# expbox.net
KiCad netlist of a schematic drawn in EAGLE
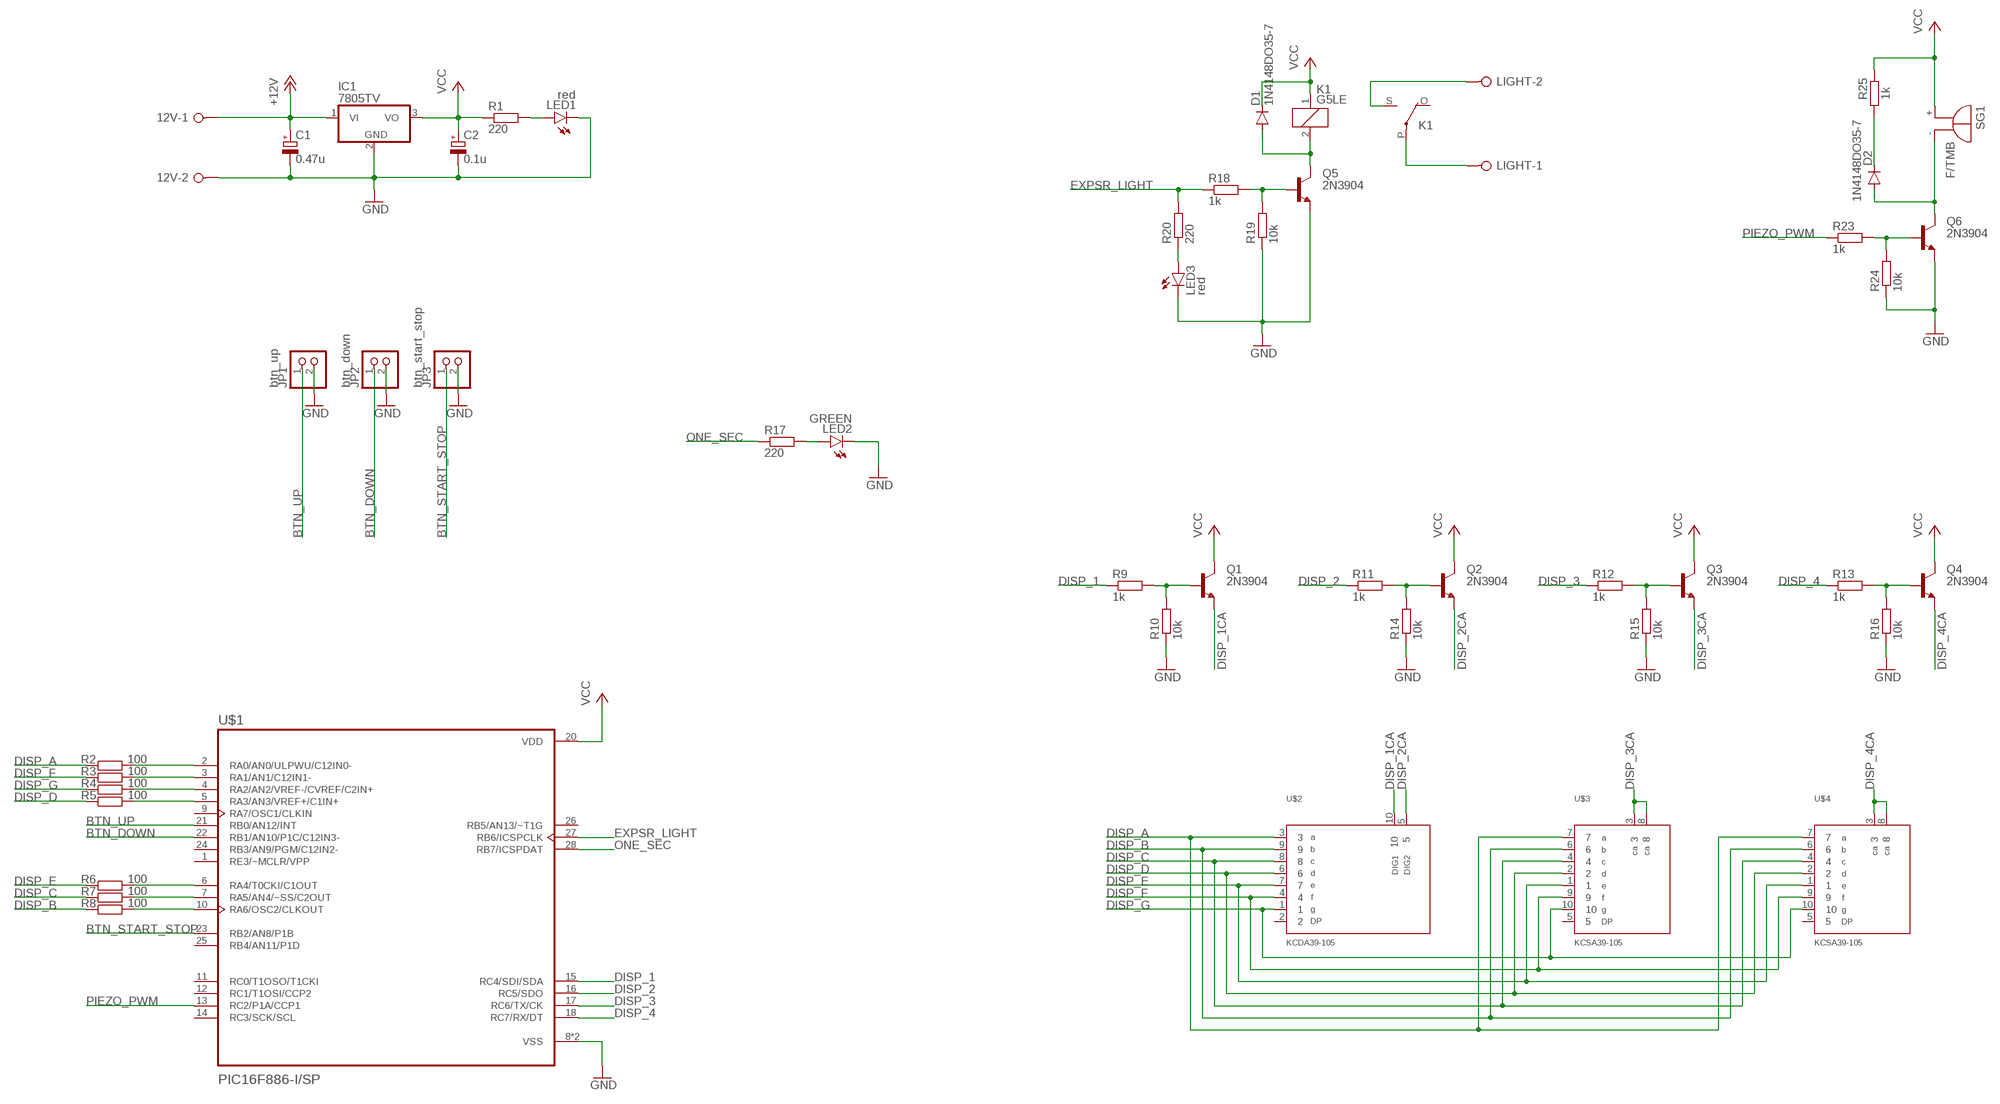
[diagram p0: schematic, sheet 1]

(export (version "E")
  (design (tool "Eeschema 10.0.6"))
  (components
    (comp (ref "12V")
      (value "W237-02P")
      (footprint "eagle-import:W237-132")
      (libsource (lib "eagle-import") (part "W237-02P"))
    )
    (comp (ref "C1")
      (value "0.47u")
      (footprint "eagle-import:E2,5-5")
      (libsource (lib "eagle-import") (part "CPOL-EUE2.5-5"))
    )
    (comp (ref "C2")
      (value "0.1u")
      (footprint "eagle-import:E2-4")
      (libsource (lib "eagle-import") (part "CPOL-EUE2-4"))
    )
    (comp (ref "D1")
      (value "1N4148DO35-7")
      (footprint "eagle-import:DO35-7")
      (libsource (lib "eagle-import") (part "1N4148DO35-7"))
    )
    (comp (ref "D2")
      (value "1N4148DO35-7")
      (footprint "eagle-import:DO35-7")
      (libsource (lib "eagle-import") (part "1N4148DO35-7"))
    )
    (comp (ref "IC1")
      (value "7805TV")
      (footprint "eagle-import:TO220V")
      (libsource (lib "eagle-import") (part "78TV05"))
    )
    (comp (ref "JP1")
      (value "btn_up")
      (footprint "eagle-import:1X02")
      (libsource (lib "eagle-import") (part "PINHD-1X2"))
    )
    (comp (ref "JP2")
      (value "btn_down")
      (footprint "eagle-import:1X02")
      (libsource (lib "eagle-import") (part "PINHD-1X2"))
    )
    (comp (ref "JP3")
      (value "btn_start_stop")
      (footprint "eagle-import:1X02")
      (libsource (lib "eagle-import") (part "PINHD-1X2"))
    )
    (comp (ref "K1")
      (value "G5LE")
      (footprint "eagle-import:G5LE")
      (libsource (lib "eagle-import") (part "G5LE"))
    )
    (comp (ref "LED1")
      (value "red")
      (footprint "eagle-import:LED3MM")
      (libsource (lib "eagle-import") (part "LED3MM"))
    )
    (comp (ref "LED2")
      (value "GREEN")
      (footprint "eagle-import:1206")
      (libsource (lib "eagle-import") (part "LEDSMT1206"))
    )
    (comp (ref "LED3")
      (value "red")
      (footprint "eagle-import:LED3MM")
      (libsource (lib "eagle-import") (part "LED3MM"))
    )
    (comp (ref "LIGHT")
      (value "W237-02P")
      (footprint "eagle-import:W237-132")
      (libsource (lib "eagle-import") (part "W237-02P"))
    )
    (comp (ref "Q1")
      (value "2N3904")
      (footprint "eagle-import:SOT23-BEC")
      (libsource (lib "eagle-import") (part "BC850SMD"))
    )
    (comp (ref "Q2")
      (value "2N3904")
      (footprint "eagle-import:SOT23-BEC")
      (libsource (lib "eagle-import") (part "BC850SMD"))
    )
    (comp (ref "Q3")
      (value "2N3904")
      (footprint "eagle-import:SOT23-BEC")
      (libsource (lib "eagle-import") (part "BC850SMD"))
    )
    (comp (ref "Q4")
      (value "2N3904")
      (footprint "eagle-import:SOT23-BEC")
      (libsource (lib "eagle-import") (part "BC850SMD"))
    )
    (comp (ref "Q5")
      (value "2N3904")
      (footprint "eagle-import:SOT23-BEC")
      (libsource (lib "eagle-import") (part "BC850SMD"))
    )
    (comp (ref "Q6")
      (value "2N3904")
      (footprint "eagle-import:SOT23-BEC")
      (libsource (lib "eagle-import") (part "BC850SMD"))
    )
    (comp (ref "R1")
      (value "220")
      (footprint "eagle-import:R0805")
      (libsource (lib "eagle-import") (part "R-EU_R0805"))
    )
    (comp (ref "R2")
      (value "100")
      (footprint "eagle-import:M1206")
      (libsource (lib "eagle-import") (part "R-EU_M1206"))
    )
    (comp (ref "R3")
      (value "100")
      (footprint "eagle-import:M1206")
      (libsource (lib "eagle-import") (part "R-EU_M1206"))
    )
    (comp (ref "R4")
      (value "100")
      (footprint "eagle-import:M1206")
      (libsource (lib "eagle-import") (part "R-EU_M1206"))
    )
    (comp (ref "R5")
      (value "100")
      (footprint "eagle-import:M1206")
      (libsource (lib "eagle-import") (part "R-EU_M1206"))
    )
    (comp (ref "R6")
      (value "100")
      (footprint "eagle-import:M1206")
      (libsource (lib "eagle-import") (part "R-EU_M1206"))
    )
    (comp (ref "R7")
      (value "100")
      (footprint "eagle-import:M1206")
      (libsource (lib "eagle-import") (part "R-EU_M1206"))
    )
    (comp (ref "R8")
      (value "100")
      (footprint "eagle-import:M1206")
      (libsource (lib "eagle-import") (part "R-EU_M1206"))
    )
    (comp (ref "R9")
      (value "1k")
      (footprint "eagle-import:R0805")
      (libsource (lib "eagle-import") (part "R-EU_R0805"))
    )
    (comp (ref "R10")
      (value "10k")
      (footprint "eagle-import:R0805")
      (libsource (lib "eagle-import") (part "R-EU_R0805"))
    )
    (comp (ref "R11")
      (value "1k")
      (footprint "eagle-import:R0805")
      (libsource (lib "eagle-import") (part "R-EU_R0805"))
    )
    (comp (ref "R12")
      (value "1k")
      (footprint "eagle-import:R0805")
      (libsource (lib "eagle-import") (part "R-EU_R0805"))
    )
    (comp (ref "R13")
      (value "1k")
      (footprint "eagle-import:R0805")
      (libsource (lib "eagle-import") (part "R-EU_R0805"))
    )
    (comp (ref "R14")
      (value "10k")
      (footprint "eagle-import:R0805")
      (libsource (lib "eagle-import") (part "R-EU_R0805"))
    )
    (comp (ref "R15")
      (value "10k")
      (footprint "eagle-import:R0805")
      (libsource (lib "eagle-import") (part "R-EU_R0805"))
    )
    (comp (ref "R16")
      (value "10k")
      (footprint "eagle-import:R0805")
      (libsource (lib "eagle-import") (part "R-EU_R0805"))
    )
    (comp (ref "R17")
      (value "220")
      (footprint "eagle-import:R0805")
      (libsource (lib "eagle-import") (part "R-EU_R0805"))
    )
    (comp (ref "R18")
      (value "1k")
      (footprint "eagle-import:R0805")
      (libsource (lib "eagle-import") (part "R-EU_R0805"))
    )
    (comp (ref "R19")
      (value "10k")
      (footprint "eagle-import:R0805")
      (libsource (lib "eagle-import") (part "R-EU_R0805"))
    )
    (comp (ref "R20")
      (value "220")
      (footprint "eagle-import:R0805")
      (libsource (lib "eagle-import") (part "R-EU_R0805"))
    )
    (comp (ref "R23")
      (value "1k")
      (footprint "eagle-import:R0805")
      (libsource (lib "eagle-import") (part "R-EU_R0805"))
    )
    (comp (ref "R24")
      (value "10k")
      (footprint "eagle-import:R0805")
      (libsource (lib "eagle-import") (part "R-EU_R0805"))
    )
    (comp (ref "R25")
      (value "1k")
      (footprint "eagle-import:R0805")
      (libsource (lib "eagle-import") (part "R-EU_R0805"))
    )
    (comp (ref "SG1")
      (value "F/TMB")
      (footprint "eagle-import:F_TMB")
      (libsource (lib "eagle-import") (part "F/TMB"))
    )
    (comp (ref "U$1")
      (value "PIC16F886-I/SP")
      (footprint "eagle-import:DIP762W46P254L3467H457Q28")
      (fields (field (name "MF") "Microchip"))
      (libsource (lib "eagle-import") (part "PIC16F886-I/SP"))
    )
    (comp (ref "U$2")
      (value "KCDA39-105")
      (footprint "eagle-import:KCDA39-105")
      (libsource (lib "eagle-import") (part "KCDA39-105"))
    )
    (comp (ref "U$3")
      (value "KCSA39-105")
      (footprint "eagle-import:KCSA39-105")
      (libsource (lib "eagle-import") (part "KCSA39-105"))
    )
    (comp (ref "U$4")
      (value "KCSA39-105")
      (footprint "eagle-import:KCSA39-105")
      (libsource (lib "eagle-import") (part "KCSA39-105"))
    )
  )
  (nets
    (net (code "1") (name "+12V") (class "Default")
      (node (ref "12V") (pin "1") (pinfunction "KL_1") (pintype "passive"))
      (node (ref "C1") (pin "+") (pinfunction "+_+") (pintype "passive"))
      (node (ref "IC1") (pin "1") (pinfunction "VI_1") (pintype "input"))
    )
    (net (code "2") (name "/BTN_DOWN") (class "Default")
      (node (ref "JP2") (pin "1") (pinfunction "1_1") (pintype "passive"))
      (node (ref "U$1") (pin "22") (pinfunction "RB1/AN10/P1C/C12IN3-_22") (pintype "input"))
    )
    (net (code "3") (name "/BTN_START_STOP") (class "Default")
      (node (ref "JP3") (pin "1") (pinfunction "1_1") (pintype "passive"))
      (node (ref "U$1") (pin "23") (pinfunction "RB2/AN8/P1B_23") (pintype "bidirectional"))
    )
    (net (code "4") (name "/BTN_UP") (class "Default")
      (node (ref "JP1") (pin "1") (pinfunction "1_1") (pintype "passive"))
      (node (ref "U$1") (pin "21") (pinfunction "RB0/AN12/INT_21") (pintype "input"))
    )
    (net (code "5") (name "/DISP_1") (class "Default")
      (node (ref "R9") (pin "1") (pinfunction "1_1") (pintype "passive"))
      (node (ref "U$1") (pin "15") (pinfunction "RC4/SDI/SDA_15") (pintype "bidirectional"))
    )
    (net (code "6") (name "/DISP_1CA") (class "Default")
      (node (ref "Q1") (pin "E") (pinfunction "E_E") (pintype "passive"))
      (node (ref "U$2") (pin "10") (pinfunction "10_10") (pintype "bidirectional"))
    )
    (net (code "7") (name "/DISP_2") (class "Default")
      (node (ref "R11") (pin "1") (pinfunction "1_1") (pintype "passive"))
      (node (ref "U$1") (pin "16") (pinfunction "RC5/SDO_16") (pintype "bidirectional"))
    )
    (net (code "8") (name "/DISP_2CA") (class "Default")
      (node (ref "Q2") (pin "E") (pinfunction "E_E") (pintype "passive"))
      (node (ref "U$2") (pin "5") (pinfunction "5_5") (pintype "bidirectional"))
    )
    (net (code "9") (name "/DISP_3") (class "Default")
      (node (ref "R12") (pin "1") (pinfunction "1_1") (pintype "passive"))
      (node (ref "U$1") (pin "17") (pinfunction "RC6/TX/CK_17") (pintype "bidirectional"))
    )
    (net (code "10") (name "/DISP_3CA") (class "Default")
      (node (ref "Q3") (pin "E") (pinfunction "E_E") (pintype "passive"))
      (node (ref "U$3") (pin "3") (pinfunction "3_3") (pintype "bidirectional"))
      (node (ref "U$3") (pin "8") (pinfunction "8_8") (pintype "bidirectional"))
    )
    (net (code "11") (name "/DISP_4") (class "Default")
      (node (ref "R13") (pin "1") (pinfunction "1_1") (pintype "passive"))
      (node (ref "U$1") (pin "18") (pinfunction "RC7/RX/DT_18") (pintype "bidirectional"))
    )
    (net (code "12") (name "/DISP_4CA") (class "Default")
      (node (ref "Q4") (pin "E") (pinfunction "E_E") (pintype "passive"))
      (node (ref "U$4") (pin "3") (pinfunction "3_3") (pintype "bidirectional"))
      (node (ref "U$4") (pin "8") (pinfunction "8_8") (pintype "bidirectional"))
    )
    (net (code "13") (name "/DISP_A") (class "Default")
      (node (ref "R2") (pin "1") (pinfunction "1_1") (pintype "passive"))
      (node (ref "U$2") (pin "3") (pinfunction "3_3") (pintype "bidirectional"))
      (node (ref "U$3") (pin "7") (pinfunction "7_7") (pintype "bidirectional"))
      (node (ref "U$4") (pin "7") (pinfunction "7_7") (pintype "bidirectional"))
    )
    (net (code "14") (name "/DISP_B") (class "Default")
      (node (ref "R8") (pin "1") (pinfunction "1_1") (pintype "passive"))
      (node (ref "U$2") (pin "9") (pinfunction "9_9") (pintype "bidirectional"))
      (node (ref "U$3") (pin "6") (pinfunction "6_6") (pintype "bidirectional"))
      (node (ref "U$4") (pin "6") (pinfunction "6_6") (pintype "bidirectional"))
    )
    (net (code "15") (name "/DISP_C") (class "Default")
      (node (ref "R7") (pin "1") (pinfunction "1_1") (pintype "passive"))
      (node (ref "U$2") (pin "8") (pinfunction "8_8") (pintype "bidirectional"))
      (node (ref "U$3") (pin "4") (pinfunction "4_4") (pintype "bidirectional"))
      (node (ref "U$4") (pin "4") (pinfunction "4_4") (pintype "bidirectional"))
    )
    (net (code "16") (name "/DISP_D") (class "Default")
      (node (ref "R5") (pin "1") (pinfunction "1_1") (pintype "passive"))
      (node (ref "U$2") (pin "6") (pinfunction "6_6") (pintype "bidirectional"))
      (node (ref "U$3") (pin "2") (pinfunction "2_2") (pintype "bidirectional"))
      (node (ref "U$4") (pin "2") (pinfunction "2_2") (pintype "bidirectional"))
    )
    (net (code "17") (name "/DISP_E") (class "Default")
      (node (ref "R6") (pin "1") (pinfunction "1_1") (pintype "passive"))
      (node (ref "U$2") (pin "7") (pinfunction "7_7") (pintype "bidirectional"))
      (node (ref "U$3") (pin "1") (pinfunction "1_1") (pintype "bidirectional"))
      (node (ref "U$4") (pin "1") (pinfunction "1_1") (pintype "bidirectional"))
    )
    (net (code "18") (name "/DISP_F") (class "Default")
      (node (ref "R3") (pin "1") (pinfunction "1_1") (pintype "passive"))
      (node (ref "U$2") (pin "4") (pinfunction "4_4") (pintype "bidirectional"))
      (node (ref "U$3") (pin "9") (pinfunction "9_9") (pintype "bidirectional"))
      (node (ref "U$4") (pin "9") (pinfunction "9_9") (pintype "bidirectional"))
    )
    (net (code "19") (name "/DISP_G") (class "Default")
      (node (ref "R4") (pin "1") (pinfunction "1_1") (pintype "passive"))
      (node (ref "U$2") (pin "1") (pinfunction "1_1") (pintype "bidirectional"))
      (node (ref "U$3") (pin "10") (pinfunction "10_10") (pintype "bidirectional"))
      (node (ref "U$4") (pin "10") (pinfunction "10_10") (pintype "bidirectional"))
    )
    (net (code "20") (name "/EXPSR_LIGHT") (class "Default")
      (node (ref "R18") (pin "1") (pinfunction "1_1") (pintype "passive"))
      (node (ref "R20") (pin "2") (pinfunction "2_2") (pintype "passive"))
      (node (ref "U$1") (pin "27") (pinfunction "RB6/ICSPCLK_27") (pintype "bidirectional"))
    )
    (net (code "21") (name "/ONE_SEC") (class "Default")
      (node (ref "R17") (pin "1") (pinfunction "1_1") (pintype "passive"))
      (node (ref "U$1") (pin "28") (pinfunction "RB7/ICSPDAT_28") (pintype "bidirectional"))
    )
    (net (code "22") (name "/PIEZO_PWM") (class "Default")
      (node (ref "R23") (pin "1") (pinfunction "1_1") (pintype "passive"))
      (node (ref "U$1") (pin "13") (pinfunction "RC2/P1A/CCP1_13") (pintype "bidirectional"))
    )
    (net (code "23") (name "GND") (class "Default")
      (node (ref "12V") (pin "2") (pinfunction "KL_2") (pintype "passive"))
      (node (ref "C1") (pin "-") (pinfunction "-_-") (pintype "passive"))
      (node (ref "C2") (pin "-") (pinfunction "-_-") (pintype "passive"))
      (node (ref "IC1") (pin "2") (pinfunction "GND_2") (pintype "passive"))
      (node (ref "JP1") (pin "2") (pinfunction "2_2") (pintype "passive"))
      (node (ref "JP2") (pin "2") (pinfunction "2_2") (pintype "passive"))
      (node (ref "JP3") (pin "2") (pinfunction "2_2") (pintype "passive"))
      (node (ref "LED1") (pin "K") (pinfunction "C_K") (pintype "passive"))
      (node (ref "LED2") (pin "C") (pinfunction "C_C") (pintype "passive"))
      (node (ref "LED3") (pin "K") (pinfunction "C_K") (pintype "passive"))
      (node (ref "Q5") (pin "E") (pinfunction "E_E") (pintype "passive"))
      (node (ref "Q6") (pin "E") (pinfunction "E_E") (pintype "passive"))
      (node (ref "R10") (pin "1") (pinfunction "1_1") (pintype "passive"))
      (node (ref "R14") (pin "1") (pinfunction "1_1") (pintype "passive"))
      (node (ref "R15") (pin "1") (pinfunction "1_1") (pintype "passive"))
      (node (ref "R16") (pin "1") (pinfunction "1_1") (pintype "passive"))
      (node (ref "R19") (pin "1") (pinfunction "1_1") (pintype "passive"))
      (node (ref "R24") (pin "1") (pinfunction "1_1") (pintype "passive"))
      (node (ref "U$1") (pin "19") (pinfunction "VSS_19") (pintype "power_in"))
      (node (ref "U$1") (pin "8") (pinfunction "VSS_8") (pintype "power_in"))
    )
    (net (code "24") (name "Net-(D1-PadA)") (class "Default")
      (node (ref "D1") (pin "A") (pinfunction "A_A") (pintype "passive"))
      (node (ref "K1") (pin "2") (pinfunction "2_2") (pintype "passive"))
      (node (ref "Q5") (pin "C") (pinfunction "C_C") (pintype "passive"))
    )
    (net (code "25") (name "Net-(D2-PadA)") (class "Default")
      (node (ref "D2") (pin "A") (pinfunction "A_A") (pintype "passive"))
      (node (ref "Q6") (pin "C") (pinfunction "C_C") (pintype "passive"))
      (node (ref "SG1") (pin "-") (pinfunction "-_-") (pintype "passive"))
    )
    (net (code "26") (name "Net-(D2-PadC)") (class "Default")
      (node (ref "D2") (pin "C") (pinfunction "C_C") (pintype "passive"))
      (node (ref "R25") (pin "1") (pinfunction "1_1") (pintype "passive"))
    )
    (net (code "27") (name "Net-(LED1-PadA)") (class "Default")
      (node (ref "LED1") (pin "A") (pinfunction "A_A") (pintype "passive"))
      (node (ref "R1") (pin "2") (pinfunction "2_2") (pintype "passive"))
    )
    (net (code "28") (name "Net-(LED2-PadA)") (class "Default")
      (node (ref "LED2") (pin "A") (pinfunction "A_A") (pintype "passive"))
      (node (ref "R17") (pin "2") (pinfunction "2_2") (pintype "passive"))
    )
    (net (code "29") (name "Net-(LED3-PadA)") (class "Default")
      (node (ref "LED3") (pin "A") (pinfunction "A_A") (pintype "passive"))
      (node (ref "R20") (pin "1") (pinfunction "1_1") (pintype "passive"))
    )
    (net (code "30") (name "Net-(LIGHTA-KL)") (class "Default")
      (node (ref "K1") (pin "P") (pinfunction "P_P") (pintype "passive"))
      (node (ref "LIGHT") (pin "1") (pinfunction "KL_1") (pintype "passive"))
    )
    (net (code "31") (name "Net-(LIGHTB-KL)") (class "Default")
      (node (ref "K1") (pin "S") (pinfunction "S_S") (pintype "passive"))
      (node (ref "LIGHT") (pin "2") (pinfunction "KL_2") (pintype "passive"))
    )
    (net (code "32") (name "Net-(Q1-PadB)") (class "Default")
      (node (ref "Q1") (pin "B") (pinfunction "B_B") (pintype "passive"))
      (node (ref "R10") (pin "2") (pinfunction "2_2") (pintype "passive"))
      (node (ref "R9") (pin "2") (pinfunction "2_2") (pintype "passive"))
    )
    (net (code "33") (name "Net-(Q2-PadB)") (class "Default")
      (node (ref "Q2") (pin "B") (pinfunction "B_B") (pintype "passive"))
      (node (ref "R11") (pin "2") (pinfunction "2_2") (pintype "passive"))
      (node (ref "R14") (pin "2") (pinfunction "2_2") (pintype "passive"))
    )
    (net (code "34") (name "Net-(Q3-PadB)") (class "Default")
      (node (ref "Q3") (pin "B") (pinfunction "B_B") (pintype "passive"))
      (node (ref "R12") (pin "2") (pinfunction "2_2") (pintype "passive"))
      (node (ref "R15") (pin "2") (pinfunction "2_2") (pintype "passive"))
    )
    (net (code "35") (name "Net-(Q4-PadB)") (class "Default")
      (node (ref "Q4") (pin "B") (pinfunction "B_B") (pintype "passive"))
      (node (ref "R13") (pin "2") (pinfunction "2_2") (pintype "passive"))
      (node (ref "R16") (pin "2") (pinfunction "2_2") (pintype "passive"))
    )
    (net (code "36") (name "Net-(Q5-PadB)") (class "Default")
      (node (ref "Q5") (pin "B") (pinfunction "B_B") (pintype "passive"))
      (node (ref "R18") (pin "2") (pinfunction "2_2") (pintype "passive"))
      (node (ref "R19") (pin "2") (pinfunction "2_2") (pintype "passive"))
    )
    (net (code "37") (name "Net-(Q6-PadB)") (class "Default")
      (node (ref "Q6") (pin "B") (pinfunction "B_B") (pintype "passive"))
      (node (ref "R23") (pin "2") (pinfunction "2_2") (pintype "passive"))
      (node (ref "R24") (pin "2") (pinfunction "2_2") (pintype "passive"))
    )
    (net (code "38") (name "Net-(U$1-RA0{slash}AN0{slash}ULPWU{slash}C12IN0-)") (class "Default")
      (node (ref "R2") (pin "2") (pinfunction "2_2") (pintype "passive"))
      (node (ref "U$1") (pin "2") (pinfunction "RA0/AN0/ULPWU/C12IN0-_2") (pintype "input"))
    )
    (net (code "39") (name "Net-(U$1-RA1{slash}AN1{slash}C12IN1-)") (class "Default")
      (node (ref "R3") (pin "2") (pinfunction "2_2") (pintype "passive"))
      (node (ref "U$1") (pin "3") (pinfunction "RA1/AN1/C12IN1-_3") (pintype "input"))
    )
    (net (code "40") (name "Net-(U$1-RA2{slash}AN2{slash}VREF-{slash}CVREF{slash}C2IN+)") (class "Default")
      (node (ref "R4") (pin "2") (pinfunction "2_2") (pintype "passive"))
      (node (ref "U$1") (pin "4") (pinfunction "RA2/AN2/VREF-/CVREF/C2IN+_4") (pintype "input"))
    )
    (net (code "41") (name "Net-(U$1-RA3{slash}AN3{slash}VREF+{slash}C1IN+)") (class "Default")
      (node (ref "R5") (pin "2") (pinfunction "2_2") (pintype "passive"))
      (node (ref "U$1") (pin "5") (pinfunction "RA3/AN3/VREF+/C1IN+_5") (pintype "input"))
    )
    (net (code "42") (name "Net-(U$1-RA4{slash}T0CKI{slash}C1OUT)") (class "Default")
      (node (ref "R6") (pin "2") (pinfunction "2_2") (pintype "passive"))
      (node (ref "U$1") (pin "6") (pinfunction "RA4/T0CKI/C1OUT_6") (pintype "bidirectional"))
    )
    (net (code "43") (name "Net-(U$1-RA5{slash}AN4{slash}~{SS{slash}C2OUT})") (class "Default")
      (node (ref "R7") (pin "2") (pinfunction "2_2") (pintype "passive"))
      (node (ref "U$1") (pin "7") (pinfunction "RA5/AN4/~{SS/C2OUT}_7") (pintype "bidirectional"))
    )
    (net (code "44") (name "Net-(U$1-RA6{slash}OSC2{slash}CLKOUT)") (class "Default")
      (node (ref "R8") (pin "2") (pinfunction "2_2") (pintype "passive"))
      (node (ref "U$1") (pin "10") (pinfunction "RA6/OSC2/CLKOUT_10") (pintype "bidirectional"))
    )
    (net (code "45") (name "VCC") (class "Default")
      (node (ref "C2") (pin "+") (pinfunction "+_+") (pintype "passive"))
      (node (ref "D1") (pin "C") (pinfunction "C_C") (pintype "passive"))
      (node (ref "IC1") (pin "3") (pinfunction "VO_3") (pintype "passive"))
      (node (ref "K1") (pin "1") (pinfunction "1_1") (pintype "passive"))
      (node (ref "Q1") (pin "C") (pinfunction "C_C") (pintype "passive"))
      (node (ref "Q2") (pin "C") (pinfunction "C_C") (pintype "passive"))
      (node (ref "Q3") (pin "C") (pinfunction "C_C") (pintype "passive"))
      (node (ref "Q4") (pin "C") (pinfunction "C_C") (pintype "passive"))
      (node (ref "R1") (pin "1") (pinfunction "1_1") (pintype "passive"))
      (node (ref "R25") (pin "2") (pinfunction "2_2") (pintype "passive"))
      (node (ref "SG1") (pin "+") (pinfunction "+_+") (pintype "passive"))
      (node (ref "U$1") (pin "20") (pinfunction "VDD_20") (pintype "power_in"))
    )
    (net (code "46") (name "unconnected-(K1-PadO)") (class "Default")
      (node (ref "K1") (pin "O") (pinfunction "O_O") (pintype "passive"))
    )
    (net (code "47") (name "unconnected-(U$1-RA7{slash}OSC1{slash}CLKIN-Pad9)") (class "Default")
      (node (ref "U$1") (pin "9") (pinfunction "RA7/OSC1/CLKIN_9") (pintype "input"))
    )
    (net (code "48") (name "unconnected-(U$1-RB3{slash}AN9{slash}PGM{slash}C12IN2--Pad24)") (class "Default")
      (node (ref "U$1") (pin "24") (pinfunction "RB3/AN9/PGM/C12IN2-_24") (pintype "input"))
    )
    (net (code "49") (name "unconnected-(U$1-RB4{slash}AN11{slash}P1D-Pad25)") (class "Default")
      (node (ref "U$1") (pin "25") (pinfunction "RB4/AN11/P1D_25") (pintype "bidirectional"))
    )
    (net (code "50") (name "unconnected-(U$1-RB5{slash}AN13{slash}~{T1G}-Pad26)") (class "Default")
      (node (ref "U$1") (pin "26") (pinfunction "RB5/AN13/~{T1G}_26") (pintype "bidirectional"))
    )
    (net (code "51") (name "unconnected-(U$1-RC0{slash}T1OSO{slash}T1CKI-Pad11)") (class "Default")
      (node (ref "U$1") (pin "11") (pinfunction "RC0/T1OSO/T1CKI_11") (pintype "bidirectional"))
    )
    (net (code "52") (name "unconnected-(U$1-RC1{slash}T1OSI{slash}CCP2-Pad12)") (class "Default")
      (node (ref "U$1") (pin "12") (pinfunction "RC1/T1OSI/CCP2_12") (pintype "bidirectional"))
    )
    (net (code "53") (name "unconnected-(U$1-RC3{slash}SCK{slash}SCL-Pad14)") (class "Default")
      (node (ref "U$1") (pin "14") (pinfunction "RC3/SCK/SCL_14") (pintype "bidirectional"))
    )
    (net (code "54") (name "unconnected-(U$1-RE3{slash}~{MCLR{slash}VPP}-Pad1)") (class "Default")
      (node (ref "U$1") (pin "1") (pinfunction "RE3/~{MCLR/VPP}_1") (pintype "input"))
    )
    (net (code "55") (name "unconnected-(U$2-Pad2)") (class "Default")
      (node (ref "U$2") (pin "2") (pinfunction "2_2") (pintype "bidirectional"))
    )
    (net (code "56") (name "unconnected-(U$3-Pad5)") (class "Default")
      (node (ref "U$3") (pin "5") (pinfunction "5_5") (pintype "bidirectional"))
    )
    (net (code "57") (name "unconnected-(U$4-Pad5)") (class "Default")
      (node (ref "U$4") (pin "5") (pinfunction "5_5") (pintype "bidirectional"))
    )
  )
)
